# 2_Smoke_detector.net
KiCad netlist of a schematic drawn in Altium Designer
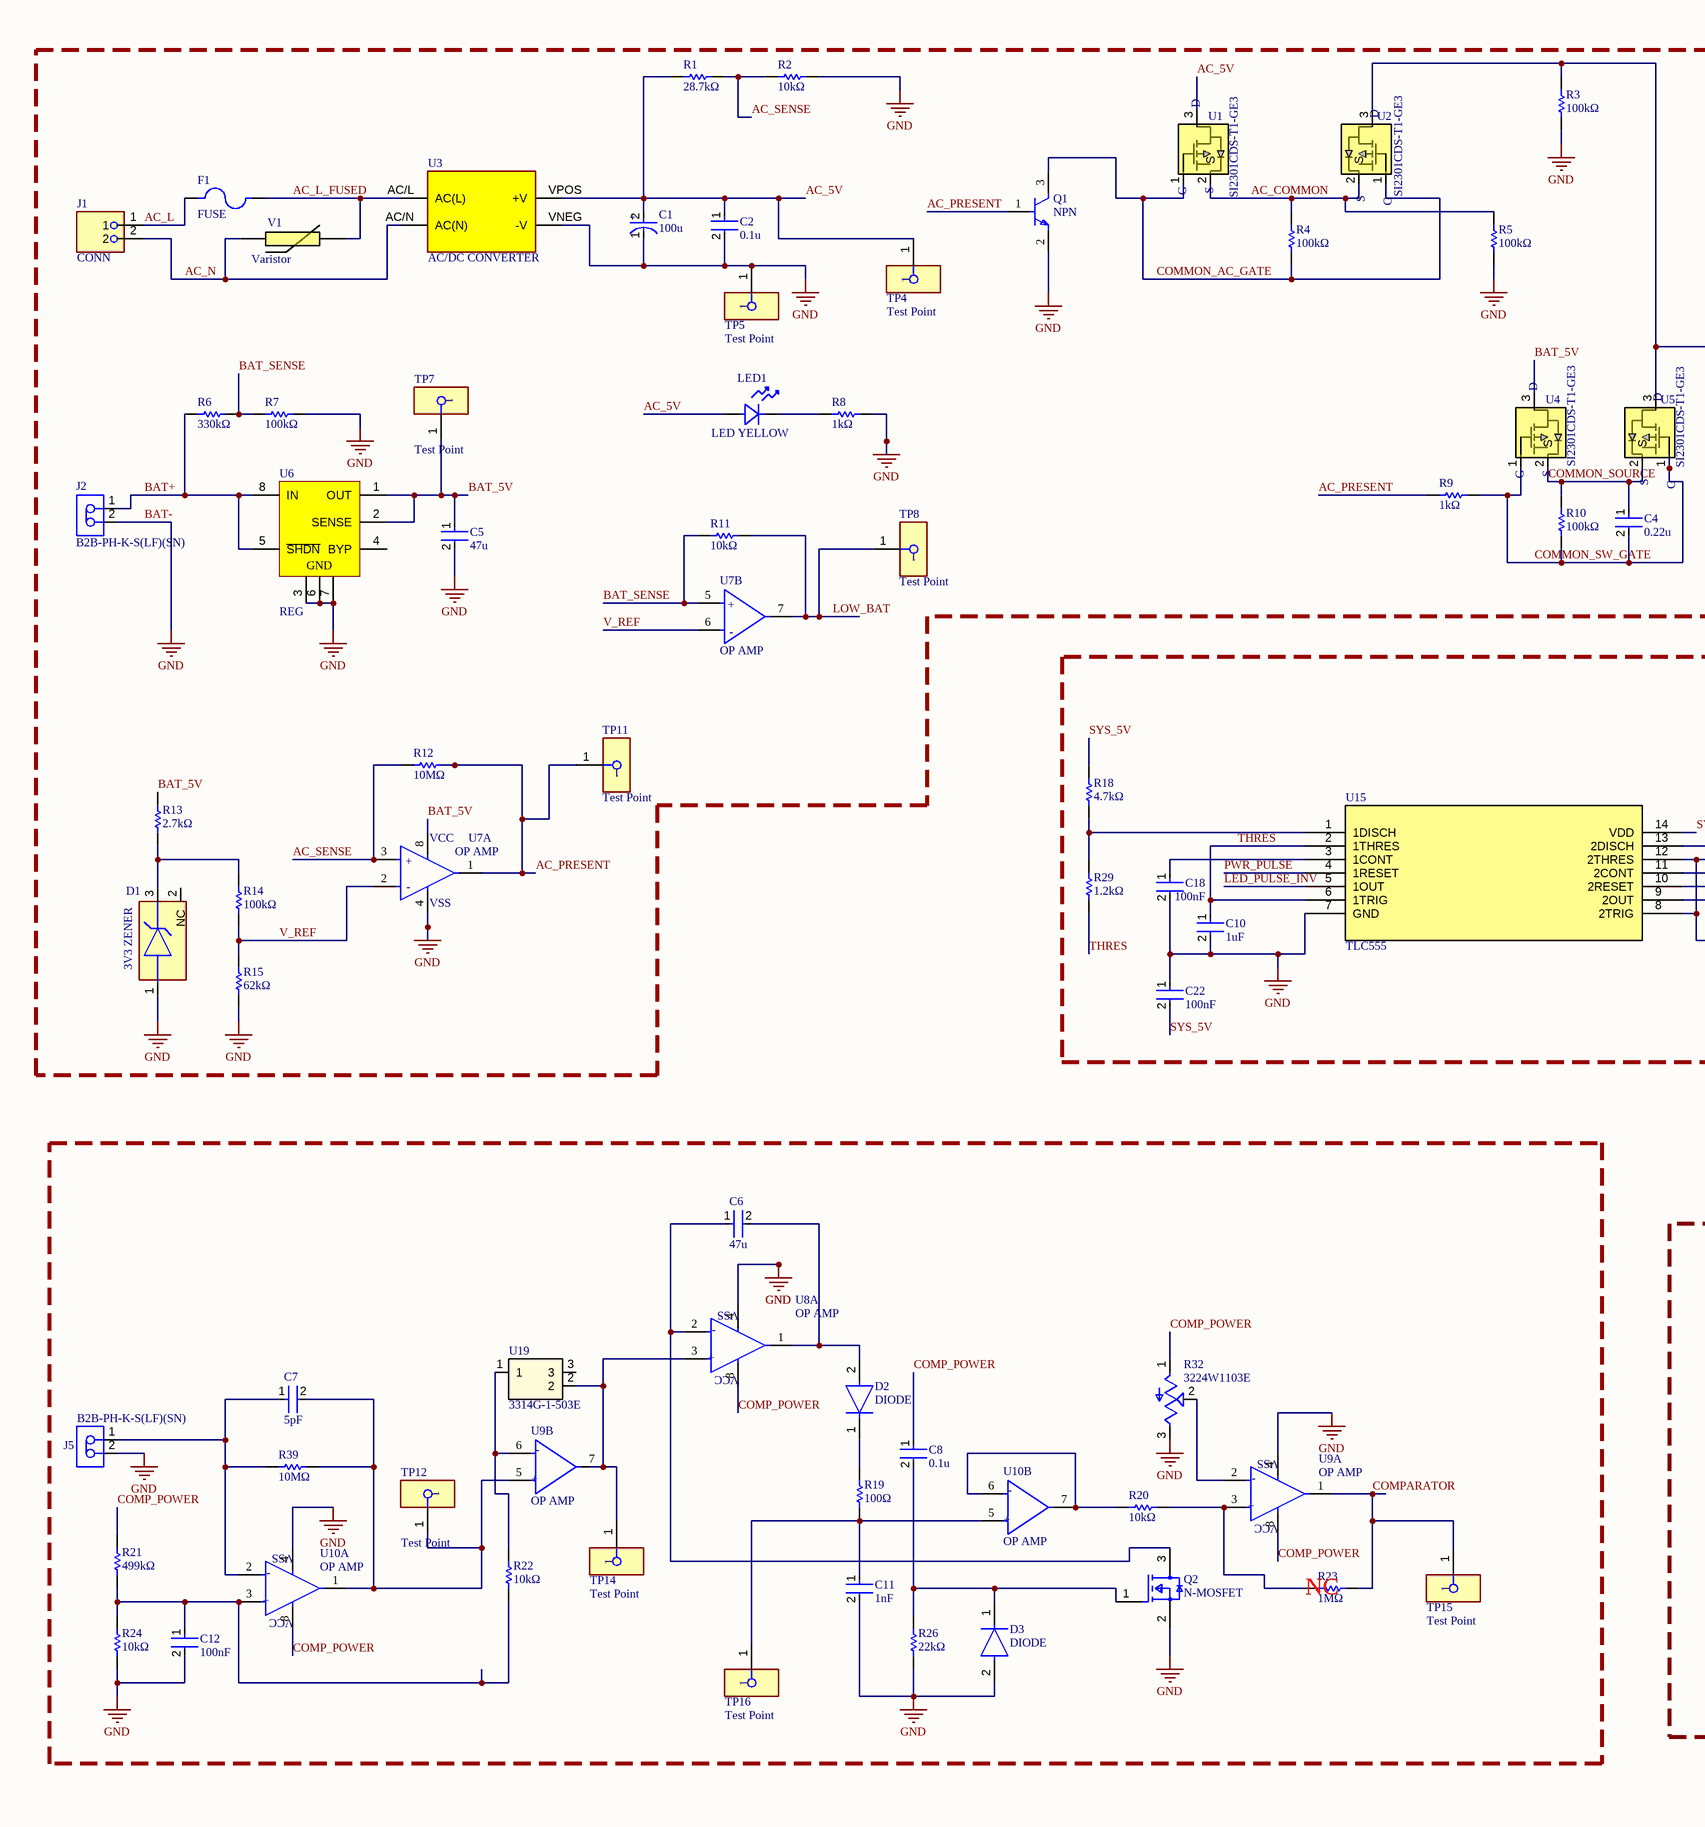
[diagram p0: 2_Smoke_detector.SchDoc, left]
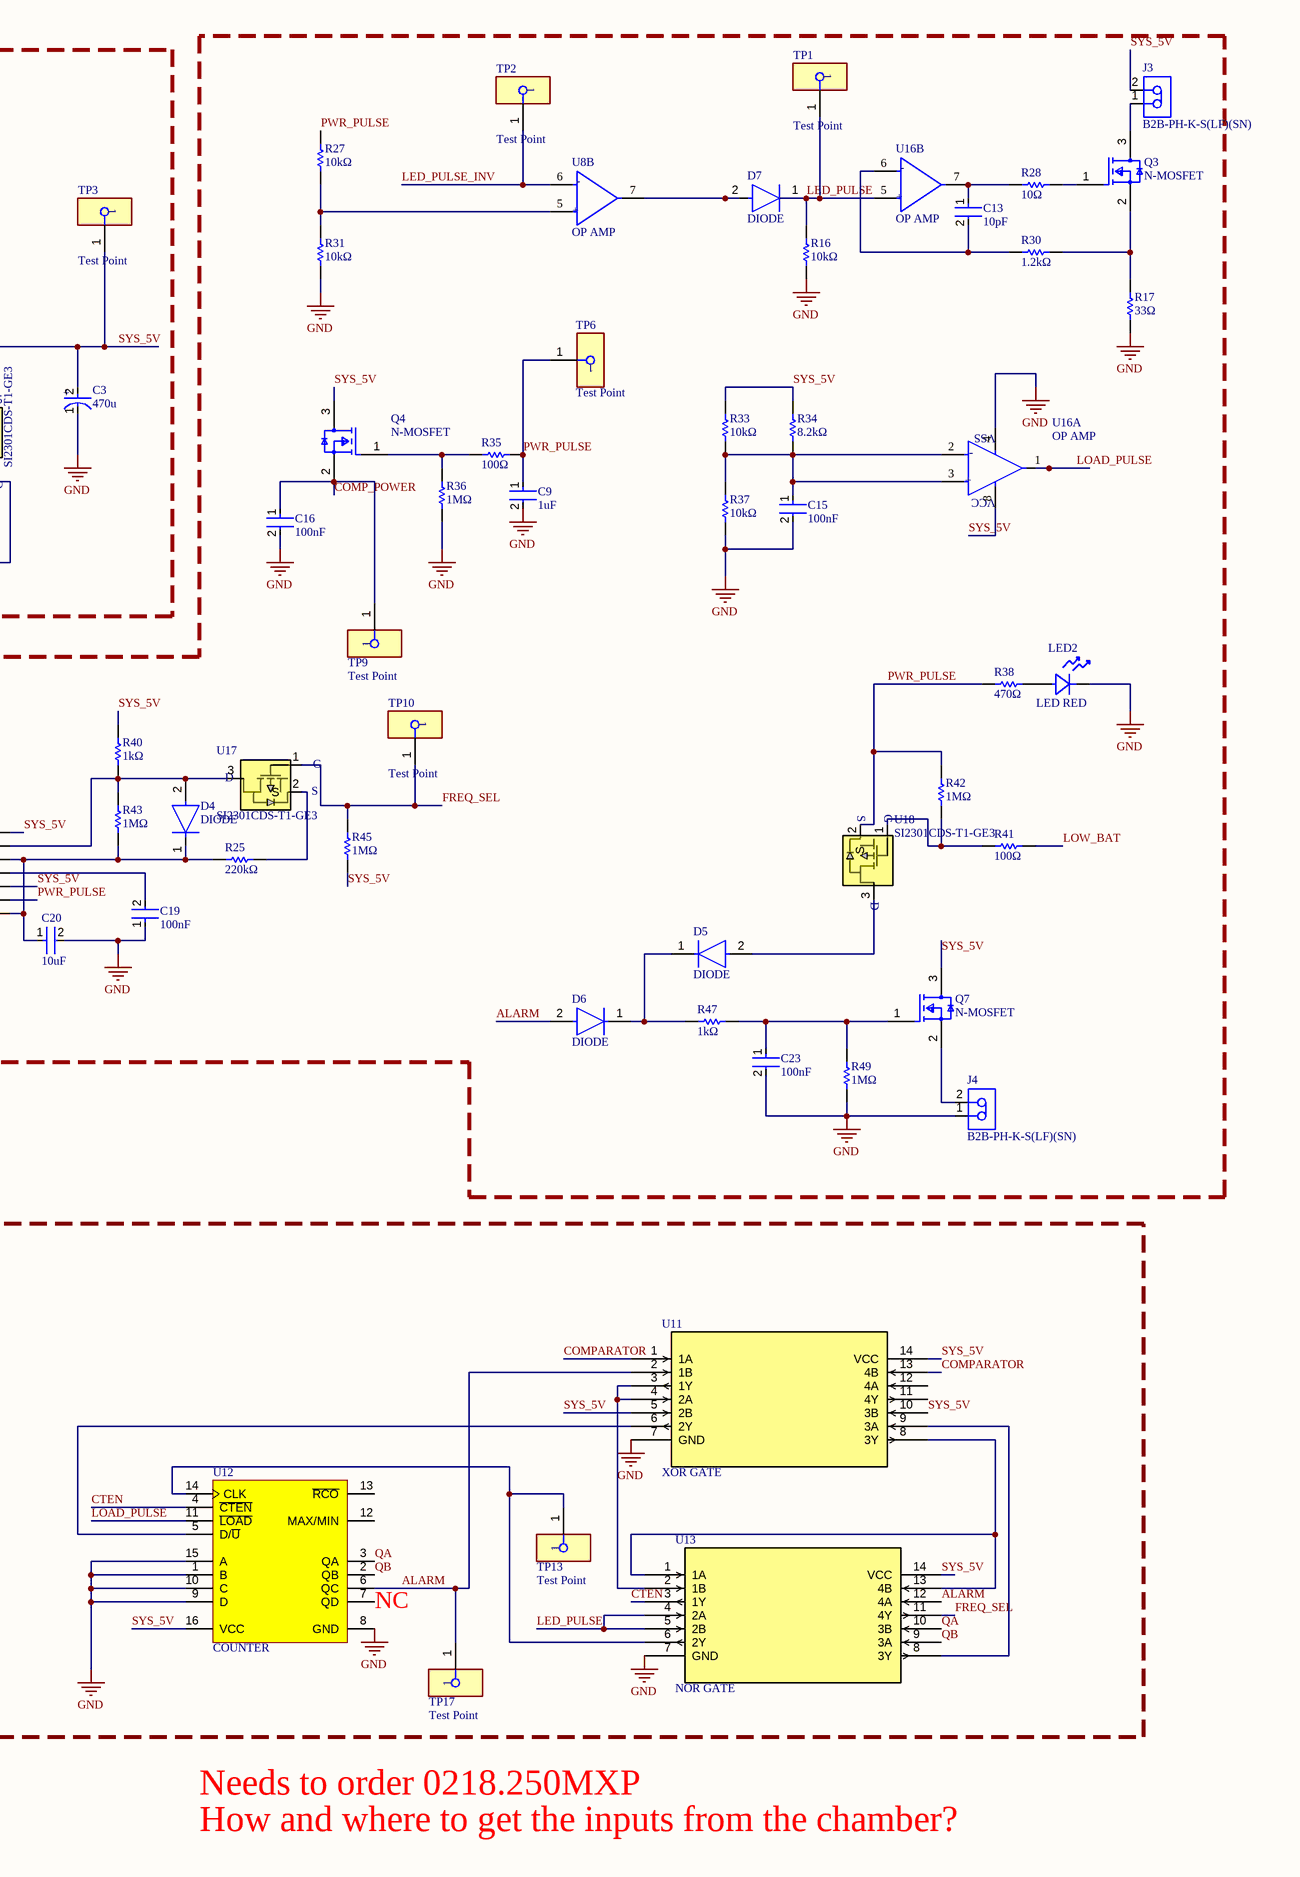
[diagram p1: 2_Smoke_detector.SchDoc, right]

(export (version "E")
  (design (tool "Eeschema 10.0.6"))
  (components
    (comp (ref "C1")
      (value "100u")
      (footprint "CAP_100u")
      (description "CAP ALUM 100uF 20% 16V SMD")
      (fields (field (name "TOLERANCE") "20%") (field (name "VOLTAGE") "16V"))
      (libsource (lib "2_Smoke_Detector") (part "EEEFT1C101AR"))
    )
    (comp (ref "C2")
      (value "0.1u")
      (footprint "0805_CER_CAP")
      (description "CAP CER 0.1uF 50V X7R 0805")
      (fields (field (name "TOLERANCE") "10%") (field (name "VOLTAGE") "50V"))
      (libsource (lib "2_Smoke_Detector") (part "CL21B104KBCNNNC"))
    )
    (comp (ref "C3")
      (value "470u")
      (footprint "Radial_SMD_CAP")
      (description "CAP ALUM 470uF ±20% 10V SMD")
      (fields
        (field (name "MANUFACTURER") "Panasonic")
        (field (name "MANUFACTURER PART NUMBER") "EEEFK1A471P")
      )
      (libsource (lib "2_Smoke_Detector") (part "EEEFK1A471P"))
    )
    (comp (ref "C4")
      (value "0.22u")
      (footprint "0805_CER_CAP")
      (description "CAP CER 0.22uF 10V X7R 0805")
      (fields
        (field (name "MANUFACTURER") "Yageo Group")
        (field (name "MANUFACTURER PART NUMBER") "CC0805KRX7R6BB224")
      )
      (libsource (lib "2_Smoke_Detector") (part "CC0805KRX7R6BB224"))
    )
    (comp (ref "C5")
      (value "47u")
      (footprint "0805_CER_CAP")
      (description "CAP CER 47uF 10V X5R 0805")
      (fields
        (field (name "MANUFACTURER") "Murata")
        (field (name "MANUFACTURER PART NUMBER") "GRM21BR61A476ME15L")
      )
      (libsource (lib "2_Smoke_Detector") (part "GRM21BR61A476ME15L"))
    )
    (comp (ref "C6")
      (value "47u")
      (footprint "0805_CER_CAP")
      (description "CAP CER 47uF 10V X5R 0805")
      (fields
        (field (name "MANUFACTURER") "Murata")
        (field (name "MANUFACTURER PART NUMBER") "GRM21BR61A476ME15L")
      )
      (libsource (lib "2_Smoke_Detector") (part "GRM21BR61A476ME15L"))
    )
    (comp (ref "C7")
      (value "5pF")
      (footprint "0805_CER_CAP")
      (description "CAP CER 5pF 50V NP0 0805")
      (fields
        (field (name "MANUFACTURER") "Yageo Group")
        (field (name "MANUFACTURER PART NUMBER") "CC0805CRNPO9BN5R0")
      )
      (libsource (lib "2_Smoke_Detector") (part "CC0805CRNPO9BN5R0"))
    )
    (comp (ref "C8")
      (value "0.1u")
      (footprint "0805_CER_CAP")
      (description "CAP CER 0.1uF 50V X7R 0805")
      (fields (field (name "TOLERANCE") "10%") (field (name "VOLTAGE") "50V"))
      (libsource (lib "2_Smoke_Detector") (part "CL21B104KBCNNNC"))
    )
    (comp (ref "C9")
      (value "1uF")
      (footprint "0805_CER_CAP")
      (description "CAP CER 1uF 50V X7R 0805")
      (fields
        (field (name "MANUFACTURER") "Samsung Electro-Mechanics")
        (field (name "MANUFACTURER PART NUMBER") "CL21B105KBFNNNE")
      )
      (libsource (lib "2_Smoke_Detector") (part "CL21B105KBFNNNE"))
    )
    (comp (ref "C10")
      (value "1uF")
      (footprint "0805_CER_CAP")
      (description "CAP CER 1uF 50V X7R 0805")
      (fields
        (field (name "MANUFACTURER") "Samsung Electro-Mechanics")
        (field (name "MANUFACTURER PART NUMBER") "CL21B105KBFNNNE")
      )
      (libsource (lib "2_Smoke_Detector") (part "CL21B105KBFNNNE"))
    )
    (comp (ref "C11")
      (value "1nF")
      (footprint "0805_CER_CAP")
      (description "CAP CER 1nF 50V X7R 0805")
      (fields
        (field (name "MANUFACTURER") "Samsung Electro-Mechanics")
        (field (name "MANUFACTURER PART NUMBER") "CL21B102KBCNNNC")
      )
      (libsource (lib "2_Smoke_Detector") (part "CL21B102KBCNNNC"))
    )
    (comp (ref "C12")
      (value "100nF")
      (footprint "0805_CER_CAP")
      (description "CAP CER 100nF 50V X7R 0805")
      (fields
        (field (name "MANUFACTURER") "Yageo Group")
        (field (name "MANUFACTURER PART NUMBER") "CC0805KRX7R9BB104")
      )
      (libsource (lib "2_Smoke_Detector") (part "CC0805KRX7R9BB104"))
    )
    (comp (ref "C13")
      (value "10pF")
      (footprint "0805_CER_CAP")
      (description "CAP CER 10pF 50V NP0 0805")
      (fields
        (field (name "MANUFACTURER") "Yageo Group")
        (field (name "MANUFACTURER PART NUMBER") "CC0805JRNPO9BN100")
      )
      (libsource (lib "2_Smoke_Detector") (part "CC0805JRNPO9BN100"))
    )
    (comp (ref "C15")
      (value "100nF")
      (footprint "0805_CER_CAP")
      (description "CAP CER 100nF 50V X7R 0805")
      (fields
        (field (name "MANUFACTURER") "Yageo Group")
        (field (name "MANUFACTURER PART NUMBER") "CC0805KRX7R9BB104")
      )
      (libsource (lib "2_Smoke_Detector") (part "CC0805KRX7R9BB104"))
    )
    (comp (ref "C16")
      (value "100nF")
      (footprint "0805_CER_CAP")
      (description "CAP CER 100nF 50V X7R 0805")
      (fields
        (field (name "MANUFACTURER") "Yageo Group")
        (field (name "MANUFACTURER PART NUMBER") "CC0805KRX7R9BB104")
      )
      (libsource (lib "2_Smoke_Detector") (part "CC0805KRX7R9BB104"))
    )
    (comp (ref "C18")
      (value "100nF")
      (footprint "0805_CER_CAP")
      (description "CAP CER 100nF 50V X7R 0805")
      (fields
        (field (name "MANUFACTURER") "Yageo Group")
        (field (name "MANUFACTURER PART NUMBER") "CC0805KRX7R9BB104")
      )
      (libsource (lib "2_Smoke_Detector") (part "CC0805KRX7R9BB104"))
    )
    (comp (ref "C19")
      (value "100nF")
      (footprint "0805_CER_CAP")
      (description "CAP CER 100nF 50V X7R 0805")
      (fields
        (field (name "MANUFACTURER") "Yageo Group")
        (field (name "MANUFACTURER PART NUMBER") "CC0805KRX7R9BB104")
      )
      (libsource (lib "2_Smoke_Detector") (part "CC0805KRX7R9BB104"))
    )
    (comp (ref "C20")
      (value "10uF")
      (footprint "0805_CER_CAP")
      (description "CAP CER 10uF 25V X5R 0805")
      (fields
        (field (name "MANUFACTURER") "TAIYO YUDEN")
        (field (name "MANUFACTURER PART NUMBER") "TMK212BBJ106KG-T")
      )
      (libsource (lib "2_Smoke_Detector") (part "TMK212BBJ106KG-T"))
    )
    (comp (ref "C22")
      (value "100nF")
      (footprint "0805_CER_CAP")
      (description "CAP CER 100nF 50V X7R 0805")
      (fields
        (field (name "MANUFACTURER") "Yageo Group")
        (field (name "MANUFACTURER PART NUMBER") "CC0805KRX7R9BB104")
      )
      (libsource (lib "2_Smoke_Detector") (part "CC0805KRX7R9BB104"))
    )
    (comp (ref "C23")
      (value "100nF")
      (footprint "0805_CER_CAP")
      (description "CAP CER 100nF 50V X7R 0805")
      (fields
        (field (name "MANUFACTURER") "Yageo Group")
        (field (name "MANUFACTURER PART NUMBER") "CC0805KRX7R9BB104")
      )
      (libsource (lib "2_Smoke_Detector") (part "CC0805KRX7R9BB104"))
    )
    (comp (ref "D1")
      (value "3V3 ZENER")
      (footprint "FP-SOT23-IPC_B_ZENER")
      (description "DIODE ZENER 3.3V 250MW TO236AB")
      (fields
        (field (name "MANUFACTURER") "Nexperia")
        (field (name "MANUFACTURER PART NUMBER") "BZX84-C3V3,215")
      )
      (libsource (lib "2_Smoke_Detector") (part "BZX84-C3V3,215"))
    )
    (comp (ref "D2")
      (value "DIODE")
      (footprint "FP-477AB-IPC_B")
      (description "DIODE STANDARD 75V 150MA SOD323F")
      (fields (field (name "MANUFACTURER") "onsemi") (field (name "MANUFACTURER PART NUMBER") "1N4148WS"))
      (libsource (lib "2_Smoke_Detector") (part "1N4148WS-E3-08"))
    )
    (comp (ref "D3")
      (value "DIODE")
      (footprint "FP-477AB-IPC_B")
      (description "DIODE STANDARD 75V 150MA SOD323F")
      (fields (field (name "MANUFACTURER") "onsemi") (field (name "MANUFACTURER PART NUMBER") "1N4148WS"))
      (libsource (lib "2_Smoke_Detector") (part "1N4148WS-E3-08"))
    )
    (comp (ref "D4")
      (value "DIODE")
      (footprint "FP-477AB-IPC_B")
      (description "DIODE STANDARD 75V 150MA SOD323F")
      (fields (field (name "MANUFACTURER") "onsemi") (field (name "MANUFACTURER PART NUMBER") "1N4148WS"))
      (libsource (lib "2_Smoke_Detector") (part "1N4148WS-E3-08"))
    )
    (comp (ref "D5")
      (value "DIODE")
      (footprint "FP-477AB-IPC_B")
      (description "DIODE STANDARD 75V 150MA SOD323F")
      (fields (field (name "MANUFACTURER") "onsemi") (field (name "MANUFACTURER PART NUMBER") "1N4148WS"))
      (libsource (lib "2_Smoke_Detector") (part "1N4148WS-E3-08"))
    )
    (comp (ref "D6")
      (value "DIODE")
      (footprint "FP-477AB-IPC_B")
      (description "DIODE STANDARD 75V 150MA SOD323F")
      (fields (field (name "MANUFACTURER") "onsemi") (field (name "MANUFACTURER PART NUMBER") "1N4148WS"))
      (libsource (lib "2_Smoke_Detector") (part "1N4148WS-E3-08"))
    )
    (comp (ref "D7")
      (value "DIODE")
      (footprint "FP-477AB-IPC_B")
      (description "DIODE STANDARD 75V 150MA SOD323F")
      (fields (field (name "MANUFACTURER") "onsemi") (field (name "MANUFACTURER PART NUMBER") "1N4148WS"))
      (libsource (lib "2_Smoke_Detector") (part "1N4148WS-E3-08"))
    )
    (comp (ref "F1")
      (value "FUSE")
      (footprint "FUSE_4628")
      (description "FUSE HLDR CARTRIDGE 250V 5A PCB")
      (fields (field (name "MANUFACTURER") "Keystone") (field (name "MANUFACTURER PART NUMBER") "4628"))
      (libsource (lib "2_Smoke_Detector") (part "4628"))
    )
    (comp (ref "J1")
      (value "CONN")
      (footprint "CONN_1715721_PXC")
      (description "TERM BLK 2P SIDE ENT 5.08MM PCB")
      (fields
        (field (name "MANUFACTURER") "Phoenix Contact")
        (field (name "MANUFACTURER PART NUMBER") "1715721")
      )
      (libsource (lib "2_Smoke_Detector") (part "1715721"))
    )
    (comp (ref "J2")
      (value "B2B-PH-K-S(LF)(SN)")
      (footprint "JST")
      (description "CONN HEADER VERT 2POS 2MM")
      (fields (field (name "MANUFACTURER") "JST") (field (name "LCSC PART NUMBER") "C131337"))
      (libsource (lib "2_Smoke_Detector") (part "B2B-PH-K-S(LF)(SN)"))
    )
    (comp (ref "J3")
      (value "B2B-PH-K-S(LF)(SN)")
      (footprint "JST")
      (description "CONN HEADER VERT 2POS 2MM")
      (fields (field (name "MANUFACTURER") "JST") (field (name "LCSC PART NUMBER") "C131337"))
      (libsource (lib "2_Smoke_Detector") (part "B2B-PH-K-S(LF)(SN)"))
    )
    (comp (ref "J4")
      (value "B2B-PH-K-S(LF)(SN)")
      (footprint "JST")
      (description "CONN HEADER VERT 2POS 2MM")
      (fields (field (name "MANUFACTURER") "JST") (field (name "LCSC PART NUMBER") "C131337"))
      (libsource (lib "2_Smoke_Detector") (part "B2B-PH-K-S(LF)(SN)"))
    )
    (comp (ref "J5")
      (value "B2B-PH-K-S(LF)(SN)")
      (footprint "JST")
      (description "CONN HEADER VERT 2POS 2MM")
      (fields (field (name "MANUFACTURER") "JST") (field (name "LCSC PART NUMBER") "C131337"))
      (libsource (lib "2_Smoke_Detector") (part "B2B-PH-K-S(LF)(SN)"))
    )
    (comp (ref "LED1")
      (value "LED YELLOW")
      (footprint "LED_C503B-RCN-030C503B-ACN-030_CRW")
      (description "LED AMBER CLEAR 5MM ROUND T/H")
      (fields
        (field (name "MANUFACTURER_PART_NUMBER") "C503B-ACN-CY0Z0252-030")
        (field (name "COPYRIGHT") "Copyright (C) 2025 Ultra Librarian. All rights reserved.")
      )
      (libsource (lib "2_Smoke_Detector") (part "C503B-ACN-CY0Z0252-030"))
    )
    (comp (ref "LED2")
      (value "LED RED")
      (footprint "LED_C503B-RCN-030C503B-ACN-030_CRW")
      (description "LED AMBER CLEAR 5MM ROUND T/H")
      (fields
        (field (name "MANUFACTURER_PART_NUMBER") "C503B-ACN-CY0Z0252-030")
        (field (name "COPYRIGHT") "Copyright (C) 2025 Ultra Librarian. All rights reserved.")
      )
      (libsource (lib "2_Smoke_Detector") (part "C503B-ACN-CY0Z0252-030"))
    )
    (comp (ref "Q1")
      (value "NPN")
      (footprint "FP-SOT323-IPC_B")
      (description "TRANS NPN 45V 0.1A SOT-323")
      (fields
        (field (name "MANUFACTURER") "Nexperia")
        (field (name "MANUFACTURER PART NUMBER") "BC847BW,115")
      )
      (libsource (lib "2_Smoke_Detector") (part "BC847BW,115"))
    )
    (comp (ref "Q2")
      (value "N-MOSFET")
      (footprint "SOT23_TOS")
      (description "MOSFET N-CH 30V 5.7A SOT23-3L")
      (fields
        (field (name "MANUFACTURER") "Alpha & Omega Semiconductor")
        (field (name "MANUFACTURER PART NUMBER") "AO3400A")
      )
      (libsource (lib "2_Smoke_Detector") (part "AO3400A"))
    )
    (comp (ref "Q3")
      (value "N-MOSFET")
      (footprint "SOT23_TOS")
      (description "MOSFET N-CH 30V 5.7A SOT23-3L")
      (fields
        (field (name "MANUFACTURER") "Alpha & Omega Semiconductor")
        (field (name "MANUFACTURER PART NUMBER") "AO3400A")
      )
      (libsource (lib "2_Smoke_Detector") (part "AO3400A"))
    )
    (comp (ref "Q4")
      (value "N-MOSFET")
      (footprint "SOT23_TOS")
      (description "MOSFET N-CH 30V 5.7A SOT23-3L")
      (fields
        (field (name "MANUFACTURER") "Alpha & Omega Semiconductor")
        (field (name "MANUFACTURER PART NUMBER") "AO3400A")
      )
      (libsource (lib "2_Smoke_Detector") (part "AO3400A"))
    )
    (comp (ref "Q7")
      (value "N-MOSFET")
      (footprint "SOT23_TOS")
      (description "MOSFET N-CH 30V 5.7A SOT23-3L")
      (fields
        (field (name "MANUFACTURER") "Alpha & Omega Semiconductor")
        (field (name "MANUFACTURER PART NUMBER") "AO3400A")
      )
      (libsource (lib "2_Smoke_Detector") (part "AO3400A"))
    )
    (comp (ref "R1")
      (value "28.7kΩ")
      (footprint "0805_RES")
      (description "RES 28.7kΩ 0.1% 1/8W 0805")
      (fields
        (field (name "MANUFACTURER") "Yageo Group")
        (field (name "MANUFACTURER PART NUMBER") "RT0805BRD0728K7L")
      )
      (libsource (lib "2_Smoke_Detector") (part "RT0805BRD0728K7L"))
    )
    (comp (ref "R2")
      (value "10kΩ")
      (footprint "0805_RES")
      (description "RES 10kΩ 1% 1/8W 0805")
      (fields
        (field (name "MANUFACTURER") "Vishay")
        (field (name "MANUFACTURER PART NUMBER") "CRCW080510K0FKEA")
      )
      (libsource (lib "2_Smoke_Detector") (part "CRCW080510K0FKEA"))
    )
    (comp (ref "R3")
      (value "100kΩ")
      (footprint "0805_RES")
      (description "RES 100kΩ 1% 1/8W 0805")
      (fields (field (name "TOLERANCE") "1%") (field (name "LCSC PART NUMBER") "C844935"))
      (libsource (lib "2_Smoke_Detector") (part "CRCW0805100KFKEA"))
    )
    (comp (ref "R4")
      (value "100kΩ")
      (footprint "0805_RES")
      (description "RES 100kΩ 1% 1/8W 0805")
      (fields (field (name "TOLERANCE") "1%") (field (name "LCSC PART NUMBER") "C844935"))
      (libsource (lib "2_Smoke_Detector") (part "CRCW0805100KFKEA"))
    )
    (comp (ref "R5")
      (value "100kΩ")
      (footprint "0805_RES")
      (description "RES 100kΩ 1% 1/8W 0805")
      (fields (field (name "TOLERANCE") "1%") (field (name "LCSC PART NUMBER") "C844935"))
      (libsource (lib "2_Smoke_Detector") (part "CRCW0805100KFKEA"))
    )
    (comp (ref "R6")
      (value "330kΩ")
      (footprint "0805_RES")
      (description "RES 330kΩ 1% 1/8W 0805")
      (fields
        (field (name "MANUFACTURER") "Yageo Group")
        (field (name "MANUFACTURER PART NUMBER") "RC0805FR-07330KL")
      )
      (libsource (lib "2_Smoke_Detector") (part "RC0805FR-07330KL"))
    )
    (comp (ref "R7")
      (value "100kΩ")
      (footprint "0805_RES")
      (description "RES 100kΩ 1% 1/8W 0805")
      (fields (field (name "TOLERANCE") "1%") (field (name "LCSC PART NUMBER") "C844935"))
      (libsource (lib "2_Smoke_Detector") (part "CRCW0805100KFKEA"))
    )
    (comp (ref "R8")
      (value "1kΩ")
      (footprint "0805_RES")
      (description "RES 1kΩ 1% 1/8W 0805")
      (fields (field (name "PART NUMBER") "CRCW08051K00FKEA") (field (name "MANUFACTURER") "Vishay Dale"))
      (libsource (lib "2_Smoke_Detector") (part "CRCW08051K00FKEA"))
    )
    (comp (ref "R9")
      (value "1kΩ")
      (footprint "0805_RES")
      (description "RES 1kΩ 1% 1/8W 0805")
      (fields (field (name "PART NUMBER") "CRCW08051K00FKEA") (field (name "MANUFACTURER") "Vishay Dale"))
      (libsource (lib "2_Smoke_Detector") (part "CRCW08051K00FKEA"))
    )
    (comp (ref "R10")
      (value "100kΩ")
      (footprint "0805_RES")
      (description "RES 100kΩ 1% 1/8W 0805")
      (fields (field (name "TOLERANCE") "1%") (field (name "LCSC PART NUMBER") "C844935"))
      (libsource (lib "2_Smoke_Detector") (part "CRCW0805100KFKEA"))
    )
    (comp (ref "R11")
      (value "10kΩ")
      (footprint "0805_RES")
      (description "RES 10kΩ 1% 1/8W 0805")
      (fields
        (field (name "MANUFACTURER") "Vishay")
        (field (name "MANUFACTURER PART NUMBER") "CRCW080510K0FKEA")
      )
      (libsource (lib "2_Smoke_Detector") (part "CRCW080510K0FKEA"))
    )
    (comp (ref "R12")
      (value "10MΩ")
      (footprint "0805_RES")
      (description "RES 10MΩ 1% 1/8W 0805")
      (fields
        (field (name "MANUFACTURER") "Vishay")
        (field (name "MANUFACTURER PART NUMBER") "CRCW080510M0FKEA")
      )
      (libsource (lib "2_Smoke_Detector") (part "CRCW080510M0FKEA"))
    )
    (comp (ref "R13")
      (value "2.7kΩ")
      (footprint "0805_RES")
      (description "RES 2.7kΩ 1% 1/8W 0805")
      (fields (field (name "TOLERANCE") "1%") (field (name "LCSC PART NUMBER") "C844836"))
      (libsource (lib "2_Smoke_Detector") (part "CRCW08052K70FKEA"))
    )
    (comp (ref "R14")
      (value "100kΩ")
      (footprint "0805_RES")
      (description "RES 100kΩ 1% 1/8W 0805")
      (fields (field (name "TOLERANCE") "1%") (field (name "LCSC PART NUMBER") "C844935"))
      (libsource (lib "2_Smoke_Detector") (part "CRCW0805100KFKEA"))
    )
    (comp (ref "R15")
      (value "62kΩ")
      (footprint "0805_RES")
      (description "RES 62kΩ 1% 1/8W 0805")
      (fields
        (field (name "MANUFACTURER") "Vishay")
        (field (name "MANUFACTURER PART NUMBER") "CRCW080562K0FKEA")
      )
      (libsource (lib "2_Smoke_Detector") (part "CRCW080562K0FKEA"))
    )
    (comp (ref "R16")
      (value "10kΩ")
      (footprint "0805_RES")
      (description "RES 10kΩ 1% 1/8W 0805")
      (fields
        (field (name "MANUFACTURER") "Vishay")
        (field (name "MANUFACTURER PART NUMBER") "CRCW080510K0FKEA")
      )
      (libsource (lib "2_Smoke_Detector") (part "CRCW080510K0FKEA"))
    )
    (comp (ref "R17")
      (value "33Ω")
      (footprint "0805_RES")
      (description "RES SMD 33Ω  1% 1/2W 0805")
      (fields
        (field (name "MANUFACTURER_PART_NUMBER") "CRCW080533R0FKEAHP")
        (field (name "LCSC PART NUMBER") "C843988")
        (field (name "COPYRIGHT") "Copyright (C) 2026 Ultra Librarian. All rights reserved.")
      )
      (libsource (lib "2_Smoke_Detector") (part "CRCW080533R0FKEAHP"))
    )
    (comp (ref "R18")
      (value "4.7kΩ")
      (footprint "0805_RES")
      (description "RES 4.7kΩ 1% 1/8W 0805")
      (fields (field (name "TOLERANCE") "1%") (field (name "LCSC PART NUMBER") "C844941"))
      (libsource (lib "2_Smoke_Detector") (part "CRCW08054K70FKEA"))
    )
    (comp (ref "R19")
      (value "100Ω")
      (footprint "0805_RES")
      (description "RES 100Ω ±1% 125mW 0805")
      (fields
        (field (name "MANUFACTURER") "Vishay")
        (field (name "MANUFACTURER PART NUMBER") "CRCW0805100RFKEA")
      )
      (libsource (lib "2_Smoke_Detector") (part "CRCW0805100RFKEA"))
    )
    (comp (ref "R20")
      (value "10kΩ")
      (footprint "0805_RES")
      (description "RES 10kΩ 1% 1/8W 0805")
      (fields
        (field (name "MANUFACTURER") "Vishay")
        (field (name "MANUFACTURER PART NUMBER") "CRCW080510K0FKEA")
      )
      (libsource (lib "2_Smoke_Detector") (part "CRCW080510K0FKEA"))
    )
    (comp (ref "R21")
      (value "499kΩ")
      (footprint "0805_RES")
      (description "RES 499kΩ ±1% 125mW 0805")
      (fields
        (field (name "MANUFACTURER") "Yageo Group")
        (field (name "MANUFACTURER PART NUMBER") "RC0805FR-07499KL")
      )
      (libsource (lib "2_Smoke_Detector") (part "RC0805FR-07499KL"))
    )
    (comp (ref "R22")
      (value "10kΩ")
      (footprint "0805_RES")
      (description "RES 10kΩ 1% 1/8W 0805")
      (fields
        (field (name "MANUFACTURER") "Vishay")
        (field (name "MANUFACTURER PART NUMBER") "CRCW080510K0FKEA")
      )
      (libsource (lib "2_Smoke_Detector") (part "CRCW080510K0FKEA"))
    )
    (comp (ref "R23")
      (value "1MΩ")
      (footprint "0805_RES")
      (description "RES 1MΩ ±1% 125mW 0805")
      (fields
        (field (name "MANUFACTURER") "Yageo Group")
        (field (name "MANUFACTURER PART NUMBER") "RC0805FR-071ML")
      )
      (libsource (lib "2_Smoke_Detector") (part "RC0805FR-071ML"))
    )
    (comp (ref "R24")
      (value "10kΩ")
      (footprint "0805_RES")
      (description "RES 10kΩ 1% 1/8W 0805")
      (fields
        (field (name "MANUFACTURER") "Vishay")
        (field (name "MANUFACTURER PART NUMBER") "CRCW080510K0FKEA")
      )
      (libsource (lib "2_Smoke_Detector") (part "CRCW080510K0FKEA"))
    )
    (comp (ref "R25")
      (value "220kΩ")
      (footprint "0805_RES")
      (description "RES 220kΩ ±1% 125mW 0805")
      (fields (field (name "LCSC PART NUMBER") "C2907242"))
      (libsource (lib "2_Smoke_Detector") (part "FRC0805F2203TS"))
    )
    (comp (ref "R26")
      (value "22kΩ")
      (footprint "0805_RES")
      (description "RES 22kΩ 1% 1/8W 0805")
      (fields
        (field (name "MANUFACTURER") "Vishay")
        (field (name "MANUFACTURER PART NUMBER") "CRCW080522K0FKEAC")
      )
      (libsource (lib "2_Smoke_Detector") (part "CRCW080522K0FKEAC"))
    )
    (comp (ref "R27")
      (value "10kΩ")
      (footprint "0805_RES")
      (description "RES 10kΩ 1% 1/8W 0805")
      (fields
        (field (name "MANUFACTURER") "Vishay")
        (field (name "MANUFACTURER PART NUMBER") "CRCW080510K0FKEA")
      )
      (libsource (lib "2_Smoke_Detector") (part "CRCW080510K0FKEA"))
    )
    (comp (ref "R28")
      (value "10Ω")
      (footprint "0805_RES")
      (description "RES 10Ω ±1% 125mW 0805")
      (fields
        (field (name "MANUFACTURER") "Vishay")
        (field (name "MANUFACTURER PART NUMBER") "CRCW080510R0FKEA")
      )
      (libsource (lib "2_Smoke_Detector") (part "CRCW080510R0FKEA"))
    )
    (comp (ref "R29")
      (value "1.2kΩ")
      (footprint "0805_RES")
      (description "RES 1.2kΩ ±5% 125mW 0805")
      (fields (field (name "LCSC PART NUMBER") "C2933520"))
      (libsource (lib "2_Smoke_Detector") (part "FRC0805J122 TS"))
    )
    (comp (ref "R30")
      (value "1.2kΩ")
      (footprint "0805_RES")
      (description "RES 1.2kΩ ±5% 125mW 0805")
      (fields (field (name "LCSC PART NUMBER") "C2933520"))
      (libsource (lib "2_Smoke_Detector") (part "FRC0805J122 TS"))
    )
    (comp (ref "R31")
      (value "10kΩ")
      (footprint "0805_RES")
      (description "RES 10kΩ 1% 1/8W 0805")
      (fields
        (field (name "MANUFACTURER") "Vishay")
        (field (name "MANUFACTURER PART NUMBER") "CRCW080510K0FKEA")
      )
      (libsource (lib "2_Smoke_Detector") (part "CRCW080510K0FKEA"))
    )
    (comp (ref "R32")
      (value "3224W1103E")
      (footprint "TRIM_3224W1103E")
      (description "TRIMMER 10K OHM 0.25W J LEAD TOP")
      (fields (field (name "MF") "Bourns Electronics") (field (name "LCSC PART NUMBER") "C81348"))
      (libsource (lib "2_Smoke_Detector") (part "3224W1103E"))
    )
    (comp (ref "R33")
      (value "10kΩ")
      (footprint "0805_RES")
      (description "RES 10kΩ 1% 1/8W 0805")
      (fields
        (field (name "MANUFACTURER") "Vishay")
        (field (name "MANUFACTURER PART NUMBER") "CRCW080510K0FKEA")
      )
      (libsource (lib "2_Smoke_Detector") (part "CRCW080510K0FKEA"))
    )
    (comp (ref "R34")
      (value "8.2kΩ")
      (footprint "0805_RES")
      (description "RES 8.2kΩ ±1% 125mW 0805")
      (fields
        (field (name "MANUFACTURER") "Vishay")
        (field (name "MANUFACTURER PART NUMBER") "CRCW08058K20FKEA")
      )
      (libsource (lib "2_Smoke_Detector") (part "CRCW08058K20FKEA"))
    )
    (comp (ref "R35")
      (value "100Ω")
      (footprint "0805_RES")
      (description "RES 100Ω ±1% 125mW 0805")
      (fields
        (field (name "MANUFACTURER") "Vishay")
        (field (name "MANUFACTURER PART NUMBER") "CRCW0805100RFKEA")
      )
      (libsource (lib "2_Smoke_Detector") (part "CRCW0805100RFKEA"))
    )
    (comp (ref "R36")
      (value "1MΩ")
      (footprint "0805_RES")
      (description "RES 1MΩ ±1% 125mW 0805")
      (fields
        (field (name "MANUFACTURER") "Yageo Group")
        (field (name "MANUFACTURER PART NUMBER") "RC0805FR-071ML")
      )
      (libsource (lib "2_Smoke_Detector") (part "RC0805FR-071ML"))
    )
    (comp (ref "R37")
      (value "10kΩ")
      (footprint "0805_RES")
      (description "RES 10kΩ 1% 1/8W 0805")
      (fields
        (field (name "MANUFACTURER") "Vishay")
        (field (name "MANUFACTURER PART NUMBER") "CRCW080510K0FKEA")
      )
      (libsource (lib "2_Smoke_Detector") (part "CRCW080510K0FKEA"))
    )
    (comp (ref "R38")
      (value "470Ω")
      (footprint "0805_RES")
      (description "RES 470Ω 1% 1/8W 0805")
      (fields
        (field (name "MANUFACTURER") "Yageo Group")
        (field (name "MANUFACTURER PART NUMBER") "RC0805FR-07470RL")
      )
      (libsource (lib "2_Smoke_Detector") (part "RC0805FR-07470RL"))
    )
    (comp (ref "R39")
      (value "10MΩ")
      (footprint "0805_RES")
      (description "RES 10MΩ 1% 1/8W 0805")
      (fields
        (field (name "MANUFACTURER") "Vishay")
        (field (name "MANUFACTURER PART NUMBER") "CRCW080510M0FKEA")
      )
      (libsource (lib "2_Smoke_Detector") (part "CRCW080510M0FKEA"))
    )
    (comp (ref "R40")
      (value "1kΩ")
      (footprint "0805_RES")
      (description "RES 1kΩ 1% 1/8W 0805")
      (fields (field (name "PART NUMBER") "CRCW08051K00FKEA") (field (name "MANUFACTURER") "Vishay Dale"))
      (libsource (lib "2_Smoke_Detector") (part "CRCW08051K00FKEA"))
    )
    (comp (ref "R41")
      (value "100Ω")
      (footprint "0805_RES")
      (description "RES 100Ω ±1% 125mW 0805")
      (fields
        (field (name "MANUFACTURER") "Vishay")
        (field (name "MANUFACTURER PART NUMBER") "CRCW0805100RFKEA")
      )
      (libsource (lib "2_Smoke_Detector") (part "CRCW0805100RFKEA"))
    )
    (comp (ref "R42")
      (value "1MΩ")
      (footprint "0805_RES")
      (description "RES 1MΩ ±1% 125mW 0805")
      (fields
        (field (name "MANUFACTURER") "Yageo Group")
        (field (name "MANUFACTURER PART NUMBER") "RC0805FR-071ML")
      )
      (libsource (lib "2_Smoke_Detector") (part "RC0805FR-071ML"))
    )
    (comp (ref "R43")
      (value "1MΩ")
      (footprint "0805_RES")
      (description "RES 1MΩ ±1% 125mW 0805")
      (fields
        (field (name "MANUFACTURER") "Yageo Group")
        (field (name "MANUFACTURER PART NUMBER") "RC0805FR-071ML")
      )
      (libsource (lib "2_Smoke_Detector") (part "RC0805FR-071ML"))
    )
    (comp (ref "R45")
      (value "1MΩ")
      (footprint "0805_RES")
      (description "RES 1MΩ ±1% 125mW 0805")
      (fields
        (field (name "MANUFACTURER") "Yageo Group")
        (field (name "MANUFACTURER PART NUMBER") "RC0805FR-071ML")
      )
      (libsource (lib "2_Smoke_Detector") (part "RC0805FR-071ML"))
    )
    (comp (ref "R47")
      (value "1kΩ")
      (footprint "0805_RES")
      (description "RES 1kΩ 1% 1/8W 0805")
      (fields (field (name "PART NUMBER") "CRCW08051K00FKEA") (field (name "MANUFACTURER") "Vishay Dale"))
      (libsource (lib "2_Smoke_Detector") (part "CRCW08051K00FKEA"))
    )
    (comp (ref "R49")
      (value "1MΩ")
      (footprint "0805_RES")
      (description "RES 1MΩ ±1% 125mW 0805")
      (fields
        (field (name "MANUFACTURER") "Yageo Group")
        (field (name "MANUFACTURER PART NUMBER") "RC0805FR-071ML")
      )
      (libsource (lib "2_Smoke_Detector") (part "RC0805FR-071ML"))
    )
    (comp (ref "TP1")
      (value "Test Point")
      (footprint "FP-5004-MFG")
      (description "PCB TEST POINT")
      (fields (field (name "MANUFACTURER") "Keystone") (field (name "MANUFACTURER PART NUMBER") "5004"))
      (libsource (lib "") (part "5004_2"))
    )
    (comp (ref "TP2")
      (value "Test Point")
      (footprint "FP-5004-MFG")
      (description "PCB TEST POINT")
      (fields (field (name "MANUFACTURER") "Keystone") (field (name "MANUFACTURER PART NUMBER") "5004"))
      (libsource (lib "") (part "5004_2"))
    )
    (comp (ref "TP3")
      (value "Test Point")
      (footprint "FP-5004-MFG")
      (description "PCB TEST POINT")
      (fields (field (name "MANUFACTURER") "Keystone") (field (name "MANUFACTURER PART NUMBER") "5004"))
      (libsource (lib "") (part "5004_2"))
    )
    (comp (ref "TP4")
      (value "Test Point")
      (footprint "FP-5004-MFG")
      (description "PCB TEST POINT")
      (fields (field (name "MANUFACTURER") "Keystone") (field (name "MANUFACTURER PART NUMBER") "5004"))
      (libsource (lib "2_Smoke_Detector") (part "5004"))
    )
    (comp (ref "TP5")
      (value "Test Point")
      (footprint "FP-5004-MFG")
      (description "PCB TEST POINT")
      (fields (field (name "MANUFACTURER") "Keystone") (field (name "MANUFACTURER PART NUMBER") "5004"))
      (libsource (lib "2_Smoke_Detector") (part "5004"))
    )
    (comp (ref "TP6")
      (value "Test Point")
      (footprint "FP-5004-MFG")
      (description "PCB TEST POINT")
      (fields (field (name "MANUFACTURER") "Keystone") (field (name "MANUFACTURER PART NUMBER") "5004"))
      (libsource (lib "") (part "5004_1"))
    )
    (comp (ref "TP7")
      (value "Test Point")
      (footprint "FP-5004-MFG")
      (description "PCB TEST POINT")
      (fields (field (name "MANUFACTURER") "Keystone") (field (name "MANUFACTURER PART NUMBER") "5004"))
      (libsource (lib "") (part "5004_2"))
    )
    (comp (ref "TP8")
      (value "Test Point")
      (footprint "FP-5004-MFG")
      (description "PCB TEST POINT")
      (fields (field (name "MANUFACTURER") "Keystone") (field (name "MANUFACTURER PART NUMBER") "5004"))
      (libsource (lib "") (part "5004_1"))
    )
    (comp (ref "TP9")
      (value "Test Point")
      (footprint "FP-5004-MFG")
      (description "PCB TEST POINT")
      (fields (field (name "MANUFACTURER") "Keystone") (field (name "MANUFACTURER PART NUMBER") "5004"))
      (libsource (lib "2_Smoke_Detector") (part "5004"))
    )
    (comp (ref "TP10")
      (value "Test Point")
      (footprint "FP-5004-MFG")
      (description "PCB TEST POINT")
      (fields (field (name "MANUFACTURER") "Keystone") (field (name "MANUFACTURER PART NUMBER") "5004"))
      (libsource (lib "") (part "5004_2"))
    )
    (comp (ref "TP11")
      (value "Test Point")
      (footprint "FP-5004-MFG")
      (description "PCB TEST POINT")
      (fields (field (name "MANUFACTURER") "Keystone") (field (name "MANUFACTURER PART NUMBER") "5004"))
      (libsource (lib "") (part "5004_1"))
    )
    (comp (ref "TP12")
      (value "Test Point")
      (footprint "FP-5004-MFG")
      (description "PCB TEST POINT")
      (fields (field (name "MANUFACTURER") "Keystone") (field (name "MANUFACTURER PART NUMBER") "5004"))
      (libsource (lib "") (part "5004_2"))
    )
    (comp (ref "TP13")
      (value "Test Point")
      (footprint "FP-5004-MFG")
      (description "PCB TEST POINT")
      (fields (field (name "MANUFACTURER") "Keystone") (field (name "MANUFACTURER PART NUMBER") "5004"))
      (libsource (lib "2_Smoke_Detector") (part "5004"))
    )
    (comp (ref "TP14")
      (value "Test Point")
      (footprint "FP-5004-MFG")
      (description "PCB TEST POINT")
      (fields (field (name "MANUFACTURER") "Keystone") (field (name "MANUFACTURER PART NUMBER") "5004"))
      (libsource (lib "2_Smoke_Detector") (part "5004"))
    )
    (comp (ref "TP15")
      (value "Test Point")
      (footprint "FP-5004-MFG")
      (description "PCB TEST POINT")
      (fields (field (name "MANUFACTURER") "Keystone") (field (name "MANUFACTURER PART NUMBER") "5004"))
      (libsource (lib "2_Smoke_Detector") (part "5004"))
    )
    (comp (ref "TP16")
      (value "Test Point")
      (footprint "FP-5004-MFG")
      (description "PCB TEST POINT")
      (fields (field (name "MANUFACTURER") "Keystone") (field (name "MANUFACTURER PART NUMBER") "5004"))
      (libsource (lib "2_Smoke_Detector") (part "5004"))
    )
    (comp (ref "TP17")
      (value "Test Point")
      (footprint "FP-5004-MFG")
      (description "PCB TEST POINT")
      (fields (field (name "MANUFACTURER") "Keystone") (field (name "MANUFACTURER PART NUMBER") "5004"))
      (libsource (lib "2_Smoke_Detector") (part "5004"))
    )
    (comp (ref "U1")
      (value "SI2301CDS-T1-GE3")
      (footprint "TO-236_VIS")
      (description "MOSFET P-CH 20V 3.1A SOT23-3")
      (fields
        (field (name "LCSC PART NUMBER") "C10487")
        (field (name "COPYRIGHT") "Copyright (C) 2026 Ultra Librarian. All rights reserved.")
      )
      (libsource (lib "") (part "SI2301CDS-T1-GE3_2"))
    )
    (comp (ref "U2")
      (value "SI2301CDS-T1-GE3")
      (footprint "TO-236_VIS")
      (description "MOSFET P-CH 20V 3.1A SOT23-3")
      (fields
        (field (name "LCSC PART NUMBER") "C10487")
        (field (name "COPYRIGHT") "Copyright (C) 2026 Ultra Librarian. All rights reserved.")
      )
      (libsource (lib "") (part "SI2301CDS-T1-GE3_1"))
    )
    (comp (ref "U3")
      (value "AC/DC CONVERTER")
      (footprint "Smoke_detector:CONV_IRM-05-5")
      (description "AC/DC CONVERTER 5V 5W")
      (fields (field (name "MANUFACTURER") "Mean Well") (field (name "MANUFACTURER PART NUMBER") "IRM-05-5"))
      (libsource (lib "2_Smoke_Detector") (part "IRM-05-5"))
    )
    (comp (ref "U4")
      (value "SI2301CDS-T1-GE3")
      (footprint "TO-236_VIS")
      (description "MOSFET P-CH 20V 3.1A SOT23-3")
      (fields
        (field (name "LCSC PART NUMBER") "C10487")
        (field (name "COPYRIGHT") "Copyright (C) 2026 Ultra Librarian. All rights reserved.")
      )
      (libsource (lib "") (part "SI2301CDS-T1-GE3_2"))
    )
    (comp (ref "U5")
      (value "SI2301CDS-T1-GE3")
      (footprint "TO-236_VIS")
      (description "MOSFET P-CH 20V 3.1A SOT23-3")
      (fields
        (field (name "LCSC PART NUMBER") "C10487")
        (field (name "COPYRIGHT") "Copyright (C) 2026 Ultra Librarian. All rights reserved.")
      )
      (libsource (lib "") (part "SI2301CDS-T1-GE3_1"))
    )
    (comp (ref "U6")
      (value "REG")
      (footprint "SO-8_S_LIT")
      (description "IC REG LINEAR 5V 500MA 8-SO")
      (fields
        (field (name "MANUFACTURER") "Analog Devices")
        (field (name "MANUFACTURER PART NUMBER") "LT1763IS8-5#PBF")
      )
      (libsource (lib "2_Smoke_Detector") (part "LT1763IS8-5#PBF"))
    )
    (comp (ref "U7")
      (value "OP AMP")
      (footprint "IC_TLV9062_8_SOIC")
      (description "IC OP AMP 2CH 8-SOIC")
      (fields (field (name "LCSC PART NUMBER") "C398355"))
      (libsource (lib "2_Smoke_Detector") (part "TLV9062IDR"))
    )
    (comp (ref "U8")
      (value "OP AMP")
      (footprint "IC_TLV9062_8_SOIC")
      (description "IC OP AMP 2CH 8-SOIC")
      (fields (field (name "LCSC PART NUMBER") "C398355"))
      (libsource (lib "2_Smoke_Detector") (part "TLV9062IDR"))
    )
    (comp (ref "U9")
      (value "OP AMP")
      (footprint "IC_TLV9062_8_SOIC")
      (description "IC OP AMP 2CH 8-SOIC")
      (fields (field (name "LCSC PART NUMBER") "C398355"))
      (libsource (lib "2_Smoke_Detector") (part "TLV9062IDR"))
    )
    (comp (ref "U10")
      (value "OP AMP")
      (footprint "IC_TLV9062_8_SOIC")
      (description "IC OP AMP 2CH 8-SOIC")
      (fields (field (name "LCSC PART NUMBER") "C398355"))
      (libsource (lib "2_Smoke_Detector") (part "TLV9062IDR"))
    )
    (comp (ref "U11")
      (value "XOR GATE")
      (footprint "SOT108-1_NXP")
      (description "IC XOR 4-CIR 2-IN 14-SOIC")
      (fields
        (field (name "MANUFACTURER") "Nexperia")
        (field (name "MANUFACTURER PART NUMBER") "74HC86D,653")
      )
      (libsource (lib "2_Smoke_Detector") (part "74HC86D,653"))
    )
    (comp (ref "U12")
      (value "COUNTER")
      (footprint "D0016A_N")
      (description "IC BINARY COUNTER 4-BIT 16SOIC")
      (fields
        (field (name "MANUFACTURER") "Texas Instruments")
        (field (name "MANUFACTURER PART NUMBER") "SN74HC191DR")
      )
      (libsource (lib "2_Smoke_Detector") (part "SN74HC191DR"))
    )
    (comp (ref "U13")
      (value "NOR GATE")
      (footprint "SOT108-1_NXP")
      (description "IC NOR 4-CIR 2-IN 14-SOIC")
      (fields
        (field (name "MANUFACTURER") "Nexperia")
        (field (name "MANUFACTURER PART NUMBER") "74HC02D,653")
      )
      (libsource (lib "2_Smoke_Detector") (part "74HC02D,653"))
    )
    (comp (ref "U15")
      (value "TLC555")
      (footprint "D14")
      (description "IC OSC TIMER DUAL 2.1MHZ 14-SOIC")
      (fields
        (field (name "MANUFACTURER") "Texas Instruments")
        (field (name "MANUFACTURER PART NUMBER") "TLC556IDR")
      )
      (libsource (lib "2_Smoke_Detector") (part "TLC556IDR"))
    )
    (comp (ref "U16")
      (value "OP AMP")
      (footprint "IC_TLV9062_8_SOIC")
      (description "IC OP AMP 2CH 8-SOIC")
      (fields (field (name "LCSC PART NUMBER") "C398355"))
      (libsource (lib "2_Smoke_Detector") (part "TLV9062IDR"))
    )
    (comp (ref "U17")
      (value "SI2301CDS-T1-GE3")
      (footprint "TO-236_VIS")
      (description "MOSFET P-CH 20V 3.1A SOT23-3")
      (fields
        (field (name "LCSC PART NUMBER") "C10487")
        (field (name "COPYRIGHT") "Copyright (C) 2026 Ultra Librarian. All rights reserved.")
      )
      (libsource (lib "2_Smoke_Detector") (part "SI2301CDS-T1-GE3"))
    )
    (comp (ref "U18")
      (value "SI2301CDS-T1-GE3")
      (footprint "TO-236_VIS")
      (description "MOSFET P-CH 20V 3.1A SOT23-3")
      (fields
        (field (name "LCSC PART NUMBER") "C10487")
        (field (name "COPYRIGHT") "Copyright (C) 2026 Ultra Librarian. All rights reserved.")
      )
      (libsource (lib "2_Smoke_Detector") (part "SI2301CDS-T1-GE3"))
    )
    (comp (ref "U19")
      (value "3314G-1-503E")
      (footprint "3314G_BRN-M")
      (description "TRIMMER 50K OHM 0.25W GW TOP ADJ")
      (fields
        (field (name "LCSC PART NUMBER") "C719184")
        (field (name "COPYRIGHT") "Copyright (C) 2025 Ultra Librarian. All rights reserved.")
      )
      (libsource (lib "2_Smoke_Detector") (part "3314G-1-503E"))
    )
    (comp (ref "V1")
      (value "Varistor")
      (footprint "LA_14MM_LOW_LTF")
      (description "VARISTOR 430V 4.5KA DISC 14MM")
      (fields
        (field (name "MANUFACTURER_PART_NUMBER") "V275LA20AP")
        (field (name "LCSC PART NUMBER") "C70419")
        (field (name "COPYRIGHT") "Copyright (C) 2025 Ultra Librarian. All rights reserved.")
      )
      (libsource (lib "2_Smoke_Detector") (part "V275LA20AP"))
    )
  )
  (nets
    (net (code "1") (name "/AC_5V") (class "Default")
      (node (ref "C1") (pin "2") (pinfunction "A_2") (pintype "passive"))
      (node (ref "C2") (pin "1") (pinfunction "1_1") (pintype "passive"))
      (node (ref "LED1") (pin "2") (pinfunction "2_2") (pintype "passive"))
      (node (ref "R1") (pin "1") (pinfunction "1_1") (pintype "passive"))
      (node (ref "TP4") (pin "1") (pinfunction "1_1") (pintype "passive"))
      (node (ref "U1") (pin "3") (pinfunction "D_3") (pintype "passive"))
      (node (ref "U3") (pin "VPOS") (pinfunction "+V_VPOS") (pintype "passive"))
    )
    (net (code "2") (name "/AC_COMMON") (class "Default")
      (node (ref "R4") (pin "2") (pinfunction "2_2") (pintype "passive"))
      (node (ref "R5") (pin "2") (pinfunction "2_2") (pintype "passive"))
      (node (ref "U1") (pin "2") (pinfunction "S_2") (pintype "passive"))
      (node (ref "U2") (pin "2") (pinfunction "S_2") (pintype "passive"))
    )
    (net (code "3") (name "/AC_L") (class "Default")
      (node (ref "F1") (pin "1") (pinfunction "1_1") (pintype "passive"))
      (node (ref "J1") (pin "1") (pinfunction "1_1") (pintype "passive"))
    )
    (net (code "4") (name "/AC_L_FUSED") (class "Default")
      (node (ref "F1") (pin "2") (pinfunction "2_2") (pintype "passive"))
      (node (ref "U3") (pin "AC/L") (pinfunction "AC(L)_AC/L") (pintype "passive"))
      (node (ref "V1") (pin "2") (pinfunction "2_2") (pintype "passive"))
    )
    (net (code "5") (name "/AC_N") (class "Default")
      (node (ref "J1") (pin "2") (pinfunction "2_2") (pintype "passive"))
      (node (ref "U3") (pin "AC/N") (pinfunction "AC(N)_AC/N") (pintype "passive"))
      (node (ref "V1") (pin "1") (pinfunction "1_1") (pintype "passive"))
    )
    (net (code "6") (name "/AC_PRESENT") (class "Default")
      (node (ref "Q1") (pin "1") (pinfunction "B_1") (pintype "passive"))
      (node (ref "R12") (pin "2") (pinfunction "2_2") (pintype "passive"))
      (node (ref "R9") (pin "1") (pinfunction "1_1") (pintype "passive"))
      (node (ref "TP11") (pin "1") (pinfunction "1_1") (pintype "passive"))
      (node (ref "U7") (pin "1") (pinfunction "OUT1_1") (pintype "passive"))
    )
    (net (code "7") (name "/AC_SENSE") (class "Default")
      (node (ref "R1") (pin "2") (pinfunction "2_2") (pintype "passive"))
      (node (ref "R12") (pin "1") (pinfunction "1_1") (pintype "passive"))
      (node (ref "R2") (pin "1") (pinfunction "1_1") (pintype "passive"))
      (node (ref "U7") (pin "3") (pinfunction "IN1+_3") (pintype "tri_state"))
    )
    (net (code "8") (name "/ALARM") (class "Default")
      (node (ref "D6") (pin "2") (pinfunction "A_2") (pintype "passive"))
      (node (ref "TP17") (pin "1") (pinfunction "1_1") (pintype "passive"))
      (node (ref "U11") (pin "2") (pinfunction "1B_2") (pintype "passive"))
      (node (ref "U12") (pin "6") (pinfunction "QC_6") (pintype "passive"))
      (node (ref "U13") (pin "12") (pinfunction "4A_12") (pintype "passive"))
    )
    (net (code "9") (name "/BAT+") (class "Default")
      (node (ref "J2") (pin "1") (pinfunction "1_1") (pintype "passive"))
      (node (ref "R6") (pin "1") (pinfunction "1_1") (pintype "passive"))
      (node (ref "U6") (pin "5") (pinfunction "~{SHDN}_5") (pintype "passive"))
      (node (ref "U6") (pin "8") (pinfunction "IN_8") (pintype "power_in"))
    )
    (net (code "10") (name "/BAT_5V") (class "Default")
      (node (ref "C5") (pin "1") (pinfunction "1_1") (pintype "passive"))
      (node (ref "R13") (pin "2") (pinfunction "2_2") (pintype "passive"))
      (node (ref "TP7") (pin "1") (pinfunction "1_1") (pintype "passive"))
      (node (ref "U4") (pin "3") (pinfunction "D_3") (pintype "passive"))
      (node (ref "U6") (pin "1") (pinfunction "OUT_1") (pintype "power_in"))
      (node (ref "U6") (pin "2") (pinfunction "SENSE_2") (pintype "passive"))
      (node (ref "U7") (pin "8") (pinfunction "V+_8") (pintype "power_in"))
    )
    (net (code "11") (name "/BAT_SENSE") (class "Default")
      (node (ref "R11") (pin "1") (pinfunction "1_1") (pintype "passive"))
      (node (ref "R6") (pin "2") (pinfunction "2_2") (pintype "passive"))
      (node (ref "R7") (pin "1") (pinfunction "1_1") (pintype "passive"))
      (node (ref "U7") (pin "5") (pinfunction "IN2+_5") (pintype "tri_state"))
    )
    (net (code "12") (name "/COMMON_AC_GATE") (class "Default")
      (node (ref "Q1") (pin "3") (pinfunction "C_3") (pintype "passive"))
      (node (ref "R4") (pin "1") (pinfunction "1_1") (pintype "passive"))
      (node (ref "U1") (pin "1") (pinfunction "G_1") (pintype "passive"))
      (node (ref "U2") (pin "1") (pinfunction "G_1") (pintype "passive"))
    )
    (net (code "13") (name "/COMMON_SOURCE") (class "Default")
      (node (ref "C4") (pin "1") (pinfunction "1_1") (pintype "passive"))
      (node (ref "R10") (pin "2") (pinfunction "2_2") (pintype "passive"))
      (node (ref "U4") (pin "2") (pinfunction "S_2") (pintype "passive"))
      (node (ref "U5") (pin "2") (pinfunction "S_2") (pintype "passive"))
    )
    (net (code "14") (name "/COMMON_SW_GATE") (class "Default")
      (node (ref "C4") (pin "2") (pinfunction "2_2") (pintype "passive"))
      (node (ref "R10") (pin "1") (pinfunction "1_1") (pintype "passive"))
      (node (ref "R9") (pin "2") (pinfunction "2_2") (pintype "passive"))
      (node (ref "U4") (pin "1") (pinfunction "G_1") (pintype "passive"))
      (node (ref "U5") (pin "1") (pinfunction "G_1") (pintype "passive"))
    )
    (net (code "15") (name "/COMPARATOR") (class "Default")
      (node (ref "R23") (pin "2") (pinfunction "2_2") (pintype "passive"))
      (node (ref "TP15") (pin "1") (pinfunction "1_1") (pintype "passive"))
      (node (ref "U11") (pin "1") (pinfunction "1A_1") (pintype "passive"))
      (node (ref "U11") (pin "13") (pinfunction "4B_13") (pintype "passive"))
      (node (ref "U9") (pin "1") (pinfunction "OUT1_1") (pintype "passive"))
    )
    (net (code "16") (name "/COMP_POWER") (class "Default")
      (node (ref "C16") (pin "1") (pinfunction "1_1") (pintype "passive"))
      (node (ref "C8") (pin "1") (pinfunction "1_1") (pintype "passive"))
      (node (ref "Q4") (pin "2") (pinfunction "S_2") (pintype "passive"))
      (node (ref "R21") (pin "2") (pinfunction "2_2") (pintype "passive"))
      (node (ref "R32") (pin "1") (pinfunction "1_1") (pintype "passive"))
      (node (ref "TP9") (pin "1") (pinfunction "1_1") (pintype "passive"))
      (node (ref "U10") (pin "8") (pinfunction "V+_8") (pintype "power_in"))
      (node (ref "U8") (pin "8") (pinfunction "V+_8") (pintype "power_in"))
      (node (ref "U9") (pin "8") (pinfunction "V+_8") (pintype "power_in"))
    )
    (net (code "17") (name "/CTEN") (class "Default")
      (node (ref "U12") (pin "4") (pinfunction "~{CTEN}_4") (pintype "passive"))
      (node (ref "U13") (pin "3") (pinfunction "1Y_3") (pintype "passive"))
    )
    (net (code "18") (name "/FREQ_SEL") (class "Default")
      (node (ref "R45") (pin "2") (pinfunction "2_2") (pintype "passive"))
      (node (ref "TP10") (pin "1") (pinfunction "1_1") (pintype "passive"))
      (node (ref "U13") (pin "11") (pinfunction "4Y_11") (pintype "passive"))
      (node (ref "U17") (pin "1") (pinfunction "G_1") (pintype "passive"))
    )
    (net (code "19") (name "/LED_PULSE") (class "Default")
      (node (ref "D7") (pin "1") (pinfunction "C_1") (pintype "passive"))
      (node (ref "R16") (pin "2") (pinfunction "2_2") (pintype "passive"))
      (node (ref "TP1") (pin "1") (pinfunction "1_1") (pintype "passive"))
      (node (ref "U13") (pin "4") (pinfunction "2A_4") (pintype "passive"))
      (node (ref "U13") (pin "5") (pinfunction "2B_5") (pintype "passive"))
      (node (ref "U16") (pin "5") (pinfunction "IN2+_5") (pintype "tri_state"))
    )
    (net (code "20") (name "/LED_PULSE_INV") (class "Default")
      (node (ref "TP2") (pin "1") (pinfunction "1_1") (pintype "passive"))
      (node (ref "U15") (pin "5") (pinfunction "1OUT_5") (pintype "passive"))
      (node (ref "U8") (pin "6") (pinfunction "IN2-_6") (pintype "tri_state"))
    )
    (net (code "21") (name "/LOAD_PULSE") (class "Default")
      (node (ref "U12") (pin "11") (pinfunction "~{LOAD}_11") (pintype "passive"))
      (node (ref "U16") (pin "1") (pinfunction "OUT1_1") (pintype "passive"))
    )
    (net (code "22") (name "/LOW_BAT") (class "Default")
      (node (ref "R11") (pin "2") (pinfunction "2_2") (pintype "passive"))
      (node (ref "R41") (pin "2") (pinfunction "2_2") (pintype "passive"))
      (node (ref "TP8") (pin "1") (pinfunction "1_1") (pintype "passive"))
      (node (ref "U7") (pin "7") (pinfunction "OUT2_7") (pintype "passive"))
    )
    (net (code "23") (name "/PWR_PULSE") (class "Default")
      (node (ref "C9") (pin "1") (pinfunction "1_1") (pintype "passive"))
      (node (ref "R27") (pin "2") (pinfunction "2_2") (pintype "passive"))
      (node (ref "R35") (pin "2") (pinfunction "2_2") (pintype "passive"))
      (node (ref "R38") (pin "1") (pinfunction "1_1") (pintype "passive"))
      (node (ref "R42") (pin "2") (pinfunction "2_2") (pintype "passive"))
      (node (ref "TP6") (pin "1") (pinfunction "1_1") (pintype "passive"))
      (node (ref "U15") (pin "4") (pinfunction "1RESET_4") (pintype "passive"))
      (node (ref "U15") (pin "9") (pinfunction "2OUT_9") (pintype "passive"))
      (node (ref "U18") (pin "2") (pinfunction "S_2") (pintype "passive"))
    )
    (net (code "24") (name "/QA") (class "Default")
      (node (ref "U12") (pin "3") (pinfunction "QA_3") (pintype "passive"))
      (node (ref "U13") (pin "10") (pinfunction "3B_10") (pintype "passive"))
    )
    (net (code "25") (name "/QB") (class "Default")
      (node (ref "U12") (pin "2") (pinfunction "QB_2") (pintype "passive"))
      (node (ref "U13") (pin "9") (pinfunction "3A_9") (pintype "passive"))
    )
    (net (code "26") (name "/SYS_5V") (class "Default")
      (node (ref "C22") (pin "2") (pinfunction "2_2") (pintype "passive"))
      (node (ref "C3") (pin "2") (pinfunction "A_2") (pintype "passive"))
      (node (ref "J3") (pin "2") (pinfunction "2_2") (pintype "passive"))
      (node (ref "Q4") (pin "3") (pinfunction "D_3") (pintype "passive"))
      (node (ref "Q7") (pin "3") (pinfunction "D_3") (pintype "passive"))
      (node (ref "R18") (pin "2") (pinfunction "2_2") (pintype "passive"))
      (node (ref "R3") (pin "2") (pinfunction "2_2") (pintype "passive"))
      (node (ref "R33") (pin "2") (pinfunction "2_2") (pintype "passive"))
      (node (ref "R34") (pin "2") (pinfunction "2_2") (pintype "passive"))
      (node (ref "R40") (pin "2") (pinfunction "2_2") (pintype "passive"))
      (node (ref "R45") (pin "1") (pinfunction "1_1") (pintype "passive"))
      (node (ref "TP3") (pin "1") (pinfunction "1_1") (pintype "passive"))
      (node (ref "U11") (pin "10") (pinfunction "3B_10") (pintype "passive"))
      (node (ref "U11") (pin "14") (pinfunction "VCC_14") (pintype "passive"))
      (node (ref "U11") (pin "5") (pinfunction "2B_5") (pintype "passive"))
      (node (ref "U12") (pin "16") (pinfunction "VCC_16") (pintype "passive"))
      (node (ref "U13") (pin "14") (pinfunction "VCC_14") (pintype "power_in"))
      (node (ref "U15") (pin "10") (pinfunction "2RESET_10") (pintype "passive"))
      (node (ref "U15") (pin "14") (pinfunction "VDD_14") (pintype "power_in"))
      (node (ref "U16") (pin "8") (pinfunction "V+_8") (pintype "power_in"))
      (node (ref "U2") (pin "3") (pinfunction "D_3") (pintype "passive"))
      (node (ref "U5") (pin "3") (pinfunction "D_3") (pintype "passive"))
    )
    (net (code "27") (name "/THRES") (class "Default")
      (node (ref "C10") (pin "1") (pinfunction "1_1") (pintype "passive"))
      (node (ref "R29") (pin "1") (pinfunction "1_1") (pintype "passive"))
      (node (ref "U15") (pin "2") (pinfunction "1THRES_2") (pintype "passive"))
      (node (ref "U15") (pin "6") (pinfunction "1TRIG_6") (pintype "passive"))
    )
    (net (code "28") (name "/V_REF") (class "Default")
      (node (ref "R14") (pin "1") (pinfunction "1_1") (pintype "passive"))
      (node (ref "R15") (pin "2") (pinfunction "2_2") (pintype "passive"))
      (node (ref "U7") (pin "2") (pinfunction "IN1-_2") (pintype "tri_state"))
      (node (ref "U7") (pin "6") (pinfunction "IN2-_6") (pintype "tri_state"))
    )
    (net (code "29") (name "GND") (class "Default")
      (node (ref "C1") (pin "1") (pinfunction "C_1") (pintype "passive"))
      (node (ref "C10") (pin "2") (pinfunction "2_2") (pintype "passive"))
      (node (ref "C11") (pin "2") (pinfunction "2_2") (pintype "passive"))
      (node (ref "C12") (pin "2") (pinfunction "2_2") (pintype "passive"))
      (node (ref "C15") (pin "2") (pinfunction "2_2") (pintype "passive"))
      (node (ref "C16") (pin "2") (pinfunction "2_2") (pintype "passive"))
      (node (ref "C18") (pin "2") (pinfunction "2_2") (pintype "passive"))
      (node (ref "C19") (pin "1") (pinfunction "1_1") (pintype "passive"))
      (node (ref "C2") (pin "2") (pinfunction "2_2") (pintype "passive"))
      (node (ref "C20") (pin "2") (pinfunction "2_2") (pintype "passive"))
      (node (ref "C22") (pin "1") (pinfunction "1_1") (pintype "passive"))
      (node (ref "C23") (pin "2") (pinfunction "2_2") (pintype "passive"))
      (node (ref "C3") (pin "1") (pinfunction "C_1") (pintype "passive"))
      (node (ref "C5") (pin "2") (pinfunction "2_2") (pintype "passive"))
      (node (ref "C9") (pin "2") (pinfunction "2_2") (pintype "passive"))
      (node (ref "D1") (pin "1") (pinfunction "A_1") (pintype "passive"))
      (node (ref "D3") (pin "2") (pinfunction "A_2") (pintype "passive"))
      (node (ref "J2") (pin "2") (pinfunction "2_2") (pintype "passive"))
      (node (ref "J4") (pin "1") (pinfunction "1_1") (pintype "passive"))
      (node (ref "J5") (pin "2") (pinfunction "2_2") (pintype "passive"))
      (node (ref "LED2") (pin "1") (pinfunction "1_1") (pintype "passive"))
      (node (ref "Q1") (pin "2") (pinfunction "E_2") (pintype "passive"))
      (node (ref "Q2") (pin "2") (pinfunction "S_2") (pintype "passive"))
      (node (ref "R15") (pin "1") (pinfunction "1_1") (pintype "passive"))
      (node (ref "R16") (pin "1") (pinfunction "1_1") (pintype "passive"))
      (node (ref "R17") (pin "1") (pinfunction "1_1") (pintype "passive"))
      (node (ref "R2") (pin "2") (pinfunction "2_2") (pintype "passive"))
      (node (ref "R24") (pin "1") (pinfunction "1_1") (pintype "passive"))
      (node (ref "R26") (pin "1") (pinfunction "1_1") (pintype "passive"))
      (node (ref "R3") (pin "1") (pinfunction "1_1") (pintype "passive"))
      (node (ref "R31") (pin "1") (pinfunction "1_1") (pintype "passive"))
      (node (ref "R32") (pin "3") (pinfunction "3_3") (pintype "passive"))
      (node (ref "R36") (pin "1") (pinfunction "1_1") (pintype "passive"))
      (node (ref "R37") (pin "1") (pinfunction "1_1") (pintype "passive"))
      (node (ref "R49") (pin "1") (pinfunction "1_1") (pintype "passive"))
      (node (ref "R5") (pin "1") (pinfunction "1_1") (pintype "passive"))
      (node (ref "R7") (pin "2") (pinfunction "2_2") (pintype "passive"))
      (node (ref "R8") (pin "2") (pinfunction "2_2") (pintype "passive"))
      (node (ref "TP5") (pin "1") (pinfunction "1_1") (pintype "passive"))
      (node (ref "U10") (pin "4") (pinfunction "V-_4") (pintype "power_in"))
      (node (ref "U11") (pin "7") (pinfunction "GND_7") (pintype "passive"))
      (node (ref "U12") (pin "1") (pinfunction "B_1") (pintype "passive"))
      (node (ref "U12") (pin "10") (pinfunction "C_10") (pintype "passive"))
      (node (ref "U12") (pin "15") (pinfunction "A_15") (pintype "passive"))
      (node (ref "U12") (pin "8") (pinfunction "GND_8") (pintype "passive"))
      (node (ref "U12") (pin "9") (pinfunction "D_9") (pintype "passive"))
      (node (ref "U13") (pin "7") (pinfunction "GND_7") (pintype "power_in"))
      (node (ref "U15") (pin "7") (pinfunction "GND_7") (pintype "power_in"))
      (node (ref "U16") (pin "4") (pinfunction "V-_4") (pintype "power_in"))
      (node (ref "U3") (pin "VNEG") (pinfunction "-V_VNEG") (pintype "passive"))
      (node (ref "U6") (pin "3") (pinfunction "GND_3") (pintype "power_in"))
      (node (ref "U6") (pin "6") (pinfunction "GND_6") (pintype "power_in"))
      (node (ref "U6") (pin "7") (pinfunction "GND_7") (pintype "power_in"))
      (node (ref "U7") (pin "4") (pinfunction "V-_4") (pintype "power_in"))
      (node (ref "U8") (pin "4") (pinfunction "V-_4") (pintype "power_in"))
      (node (ref "U9") (pin "4") (pinfunction "V-_4") (pintype "power_in"))
    )
    (net (code "30") (name "Net-(D1-K)") (class "Default")
      (node (ref "D1") (pin "3") (pinfunction "K_3") (pintype "passive"))
      (node (ref "R13") (pin "1") (pinfunction "1_1") (pintype "passive"))
      (node (ref "R14") (pin "2") (pinfunction "2_2") (pintype "passive"))
    )
    (net (code "31") (name "Net-(D2-A)") (class "Default")
      (node (ref "C6") (pin "2") (pinfunction "2_2") (pintype "passive"))
      (node (ref "D2") (pin "2") (pinfunction "A_2") (pintype "passive"))
      (node (ref "U8") (pin "1") (pinfunction "OUT1_1") (pintype "passive"))
    )
    (net (code "32") (name "Net-(D2-C)") (class "Default")
      (node (ref "D2") (pin "1") (pinfunction "C_1") (pintype "passive"))
      (node (ref "R19") (pin "2") (pinfunction "2_2") (pintype "passive"))
    )
    (net (code "33") (name "Net-(D3-C)") (class "Default")
      (node (ref "C8") (pin "2") (pinfunction "2_2") (pintype "passive"))
      (node (ref "D3") (pin "1") (pinfunction "C_1") (pintype "passive"))
      (node (ref "Q2") (pin "1") (pinfunction "G_1") (pintype "passive"))
      (node (ref "R26") (pin "2") (pinfunction "2_2") (pintype "passive"))
    )
    (net (code "34") (name "Net-(D4-A)") (class "Default")
      (node (ref "D4") (pin "2") (pinfunction "A_2") (pintype "passive"))
      (node (ref "R40") (pin "1") (pinfunction "1_1") (pintype "passive"))
      (node (ref "R43") (pin "2") (pinfunction "2_2") (pintype "passive"))
      (node (ref "U15") (pin "13") (pinfunction "2DISCH_13") (pintype "passive"))
      (node (ref "U17") (pin "3") (pinfunction "D_3") (pintype "passive"))
    )
    (net (code "35") (name "Net-(D4-C)") (class "Default")
      (node (ref "C20") (pin "1") (pinfunction "1_1") (pintype "passive"))
      (node (ref "D4") (pin "1") (pinfunction "C_1") (pintype "passive"))
      (node (ref "R25") (pin "1") (pinfunction "1_1") (pintype "passive"))
      (node (ref "R43") (pin "1") (pinfunction "1_1") (pintype "passive"))
      (node (ref "U15") (pin "12") (pinfunction "2THRES_12") (pintype "passive"))
      (node (ref "U15") (pin "8") (pinfunction "2TRIG_8") (pintype "passive"))
    )
    (net (code "36") (name "Net-(D5-A)") (class "Default")
      (node (ref "D5") (pin "2") (pinfunction "A_2") (pintype "passive"))
      (node (ref "U18") (pin "3") (pinfunction "D_3") (pintype "passive"))
    )
    (net (code "37") (name "Net-(D5-C)") (class "Default")
      (node (ref "D5") (pin "1") (pinfunction "C_1") (pintype "passive"))
      (node (ref "D6") (pin "1") (pinfunction "C_1") (pintype "passive"))
      (node (ref "R47") (pin "1") (pinfunction "1_1") (pintype "passive"))
    )
    (net (code "38") (name "Net-(D7-A)") (class "Default")
      (node (ref "D7") (pin "2") (pinfunction "A_2") (pintype "passive"))
      (node (ref "U8") (pin "7") (pinfunction "OUT2_7") (pintype "passive"))
    )
    (net (code "39") (name "Net-(LED1-Pad1)") (class "Default")
      (node (ref "LED1") (pin "1") (pinfunction "1_1") (pintype "passive"))
      (node (ref "R8") (pin "1") (pinfunction "1_1") (pintype "passive"))
    )
    (net (code "40") (name "Net-(LED2-Pad2)") (class "Default")
      (node (ref "LED2") (pin "2") (pinfunction "2_2") (pintype "passive"))
      (node (ref "R38") (pin "2") (pinfunction "2_2") (pintype "passive"))
    )
    (net (code "41") (name "Net-(Q2-D)") (class "Default")
      (node (ref "C6") (pin "1") (pinfunction "1_1") (pintype "passive"))
      (node (ref "Q2") (pin "3") (pinfunction "D_3") (pintype "passive"))
      (node (ref "U8") (pin "2") (pinfunction "IN1-_2") (pintype "tri_state"))
    )
    (net (code "42") (name "Net-(Q3-D)") (class "Default")
      (node (ref "J3") (pin "1") (pinfunction "1_1") (pintype "passive"))
      (node (ref "Q3") (pin "3") (pinfunction "D_3") (pintype "passive"))
    )
    (net (code "43") (name "Net-(Q3-G)") (class "Default")
      (node (ref "Q3") (pin "1") (pinfunction "G_1") (pintype "passive"))
      (node (ref "R28") (pin "2") (pinfunction "2_2") (pintype "passive"))
    )
    (net (code "44") (name "Net-(Q3-S)") (class "Default")
      (node (ref "Q3") (pin "2") (pinfunction "S_2") (pintype "passive"))
      (node (ref "R17") (pin "2") (pinfunction "2_2") (pintype "passive"))
      (node (ref "R30") (pin "2") (pinfunction "2_2") (pintype "passive"))
    )
    (net (code "45") (name "Net-(Q4-G)") (class "Default")
      (node (ref "Q4") (pin "1") (pinfunction "G_1") (pintype "passive"))
      (node (ref "R35") (pin "1") (pinfunction "1_1") (pintype "passive"))
      (node (ref "R36") (pin "2") (pinfunction "2_2") (pintype "passive"))
    )
    (net (code "46") (name "Net-(Q7-G)") (class "Default")
      (node (ref "C23") (pin "1") (pinfunction "1_1") (pintype "passive"))
      (node (ref "Q7") (pin "1") (pinfunction "G_1") (pintype "passive"))
      (node (ref "R47") (pin "2") (pinfunction "2_2") (pintype "passive"))
      (node (ref "R49") (pin "2") (pinfunction "2_2") (pintype "passive"))
    )
    (net (code "47") (name "Net-(Q7-S)") (class "Default")
      (node (ref "J4") (pin "2") (pinfunction "2_2") (pintype "passive"))
      (node (ref "Q7") (pin "2") (pinfunction "S_2") (pintype "passive"))
    )
    (net (code "48") (name "Net-(U8A-IN1+)") (class "Default")
      (node (ref "TP14") (pin "1") (pinfunction "1_1") (pintype "passive"))
      (node (ref "U19") (pin "2") (pinfunction "2_2") (pintype "passive"))
      (node (ref "U8") (pin "3") (pinfunction "IN1+_3") (pintype "tri_state"))
      (node (ref "U9") (pin "7") (pinfunction "OUT2_7") (pintype "passive"))
    )
    (net (code "49") (name "Net-(U8B-IN2+)") (class "Default")
      (node (ref "R27") (pin "1") (pinfunction "1_1") (pintype "passive"))
      (node (ref "R31") (pin "2") (pinfunction "2_2") (pintype "passive"))
      (node (ref "U8") (pin "5") (pinfunction "IN2+_5") (pintype "tri_state"))
    )
    (net (code "50") (name "Net-(U9A-IN1+)") (class "Default")
      (node (ref "R20") (pin "2") (pinfunction "2_2") (pintype "passive"))
      (node (ref "R23") (pin "1") (pinfunction "1_1") (pintype "passive"))
      (node (ref "U9") (pin "3") (pinfunction "IN1+_3") (pintype "tri_state"))
    )
    (net (code "51") (name "Net-(U9A-IN1-)") (class "Default")
      (node (ref "R32") (pin "2") (pinfunction "2_2") (pintype "passive"))
      (node (ref "U9") (pin "2") (pinfunction "IN1-_2") (pintype "tri_state"))
    )
    (net (code "52") (name "Net-(U9B-IN2-)") (class "Default")
      (node (ref "R22") (pin "2") (pinfunction "2_2") (pintype "passive"))
      (node (ref "U19") (pin "1") (pinfunction "1_1") (pintype "passive"))
      (node (ref "U9") (pin "6") (pinfunction "IN2-_6") (pintype "tri_state"))
    )
    (net (code "53") (name "Net-(U10A-IN1+)") (class "Default")
      (node (ref "C12") (pin "1") (pinfunction "1_1") (pintype "passive"))
      (node (ref "R21") (pin "1") (pinfunction "1_1") (pintype "passive"))
      (node (ref "R22") (pin "1") (pinfunction "1_1") (pintype "passive"))
      (node (ref "R24") (pin "2") (pinfunction "2_2") (pintype "passive"))
      (node (ref "U10") (pin "3") (pinfunction "IN1+_3") (pintype "tri_state"))
    )
    (net (code "54") (name "Net-(U10A-IN1-)") (class "Default")
      (node (ref "C7") (pin "1") (pinfunction "1_1") (pintype "passive"))
      (node (ref "J5") (pin "1") (pinfunction "1_1") (pintype "passive"))
      (node (ref "R39") (pin "1") (pinfunction "1_1") (pintype "passive"))
      (node (ref "U10") (pin "2") (pinfunction "IN1-_2") (pintype "tri_state"))
    )
    (net (code "55") (name "Net-(U10A-OUT1)") (class "Default")
      (node (ref "C7") (pin "2") (pinfunction "2_2") (pintype "passive"))
      (node (ref "R39") (pin "2") (pinfunction "2_2") (pintype "passive"))
      (node (ref "TP12") (pin "1") (pinfunction "1_1") (pintype "passive"))
      (node (ref "U10") (pin "1") (pinfunction "OUT1_1") (pintype "passive"))
      (node (ref "U9") (pin "5") (pinfunction "IN2+_5") (pintype "tri_state"))
    )
    (net (code "56") (name "Net-(U10B-IN2+)") (class "Default")
      (node (ref "C11") (pin "1") (pinfunction "1_1") (pintype "passive"))
      (node (ref "R19") (pin "1") (pinfunction "1_1") (pintype "passive"))
      (node (ref "TP16") (pin "1") (pinfunction "1_1") (pintype "passive"))
      (node (ref "U10") (pin "5") (pinfunction "IN2+_5") (pintype "tri_state"))
    )
    (net (code "57") (name "Net-(U10B-IN2-)") (class "Default")
      (node (ref "R20") (pin "1") (pinfunction "1_1") (pintype "passive"))
      (node (ref "U10") (pin "6") (pinfunction "IN2-_6") (pintype "tri_state"))
      (node (ref "U10") (pin "7") (pinfunction "OUT2_7") (pintype "passive"))
    )
    (net (code "58") (name "Net-(U11-1Y)") (class "Default")
      (node (ref "U11") (pin "3") (pinfunction "1Y_3") (pintype "passive"))
      (node (ref "U11") (pin "4") (pinfunction "2A_4") (pintype "passive"))
      (node (ref "U13") (pin "2") (pinfunction "1B_2") (pintype "passive"))
    )
    (net (code "59") (name "Net-(U11-2Y)") (class "Default")
      (node (ref "U11") (pin "6") (pinfunction "2Y_6") (pintype "passive"))
      (node (ref "U12") (pin "5") (pinfunction "D/~{U}_5") (pintype "passive"))
    )
    (net (code "60") (name "Net-(U11-3A)") (class "Default")
      (node (ref "U11") (pin "9") (pinfunction "3A_9") (pintype "passive"))
      (node (ref "U13") (pin "8") (pinfunction "3Y_8") (pintype "passive"))
    )
    (net (code "61") (name "Net-(U11-3Y)") (class "Default")
      (node (ref "U11") (pin "8") (pinfunction "3Y_8") (pintype "passive"))
      (node (ref "U13") (pin "1") (pinfunction "1A_1") (pintype "passive"))
      (node (ref "U13") (pin "13") (pinfunction "4B_13") (pintype "passive"))
    )
    (net (code "62") (name "Net-(U12-CLK)") (class "Default")
      (node (ref "TP13") (pin "1") (pinfunction "1_1") (pintype "passive"))
      (node (ref "U12") (pin "14") (pinfunction "CLK_14") (pintype "passive"))
      (node (ref "U13") (pin "6") (pinfunction "2Y_6") (pintype "passive"))
    )
    (net (code "63") (name "Net-(U15-1CONT)") (class "Default")
      (node (ref "C18") (pin "1") (pinfunction "1_1") (pintype "passive"))
      (node (ref "U15") (pin "3") (pinfunction "1CONT_3") (pintype "passive"))
    )
    (net (code "64") (name "Net-(U15-1DISCH)") (class "Default")
      (node (ref "R18") (pin "1") (pinfunction "1_1") (pintype "passive"))
      (node (ref "R29") (pin "2") (pinfunction "2_2") (pintype "passive"))
      (node (ref "U15") (pin "1") (pinfunction "1DISCH_1") (pintype "passive"))
    )
    (net (code "65") (name "Net-(U15-2CONT)") (class "Default")
      (node (ref "C19") (pin "2") (pinfunction "2_2") (pintype "passive"))
      (node (ref "U15") (pin "11") (pinfunction "2CONT_11") (pintype "passive"))
    )
    (net (code "66") (name "Net-(U16A-IN1+)") (class "Default")
      (node (ref "C15") (pin "1") (pinfunction "1_1") (pintype "passive"))
      (node (ref "R33") (pin "1") (pinfunction "1_1") (pintype "passive"))
      (node (ref "R34") (pin "1") (pinfunction "1_1") (pintype "passive"))
      (node (ref "R37") (pin "2") (pinfunction "2_2") (pintype "passive"))
      (node (ref "U16") (pin "2") (pinfunction "IN1-_2") (pintype "tri_state"))
      (node (ref "U16") (pin "3") (pinfunction "IN1+_3") (pintype "tri_state"))
    )
    (net (code "67") (name "Net-(U16B-IN2-)") (class "Default")
      (node (ref "C13") (pin "2") (pinfunction "2_2") (pintype "passive"))
      (node (ref "R30") (pin "1") (pinfunction "1_1") (pintype "passive"))
      (node (ref "U16") (pin "6") (pinfunction "IN2-_6") (pintype "tri_state"))
    )
    (net (code "68") (name "Net-(U16B-OUT2)") (class "Default")
      (node (ref "C13") (pin "1") (pinfunction "1_1") (pintype "passive"))
      (node (ref "R28") (pin "1") (pinfunction "1_1") (pintype "passive"))
      (node (ref "U16") (pin "7") (pinfunction "OUT2_7") (pintype "passive"))
    )
    (net (code "69") (name "Net-(U17-S)") (class "Default")
      (node (ref "R25") (pin "2") (pinfunction "2_2") (pintype "passive"))
      (node (ref "U17") (pin "2") (pinfunction "S_2") (pintype "passive"))
    )
    (net (code "70") (name "Net-(U18-G)") (class "Default")
      (node (ref "R41") (pin "1") (pinfunction "1_1") (pintype "passive"))
      (node (ref "R42") (pin "1") (pinfunction "1_1") (pintype "passive"))
      (node (ref "U18") (pin "1") (pinfunction "G_1") (pintype "passive"))
    )
    (net (code "71") (name "unconnected-(D1-NC-Pad2)") (class "Default")
      (node (ref "D1") (pin "2") (pinfunction "NC_2") (pintype "passive"))
    )
    (net (code "72") (name "unconnected-(U6-BYP-Pad4)") (class "Default")
      (node (ref "U6") (pin "4") (pinfunction "BYP_4") (pintype "passive"))
    )
    (net (code "73") (name "unconnected-(U11-4A-Pad12)") (class "Default")
      (node (ref "U11") (pin "12") (pinfunction "4A_12") (pintype "passive"))
    )
    (net (code "74") (name "unconnected-(U11-4Y-Pad11)") (class "Default")
      (node (ref "U11") (pin "11") (pinfunction "4Y_11") (pintype "passive"))
    )
    (net (code "75") (name "unconnected-(U12-MAX{slash}MIN-Pad12)") (class "Default")
      (node (ref "U12") (pin "12") (pinfunction "MAX/MIN_12") (pintype "passive"))
    )
    (net (code "76") (name "unconnected-(U12-QD-Pad7)") (class "Default")
      (node (ref "U12") (pin "7") (pinfunction "QD_7") (pintype "passive"))
    )
    (net (code "77") (name "unconnected-(U12-~{RCO}-Pad13)") (class "Default")
      (node (ref "U12") (pin "13") (pinfunction "~{RCO}_13") (pintype "passive"))
    )
    (net (code "78") (name "unconnected-(U19-Pad3)") (class "Default")
      (node (ref "U19") (pin "3") (pinfunction "3_3") (pintype "passive"))
    )
  )
)
